# XL6009.net
KiCad netlist of a schematic drawn in Altium Designer
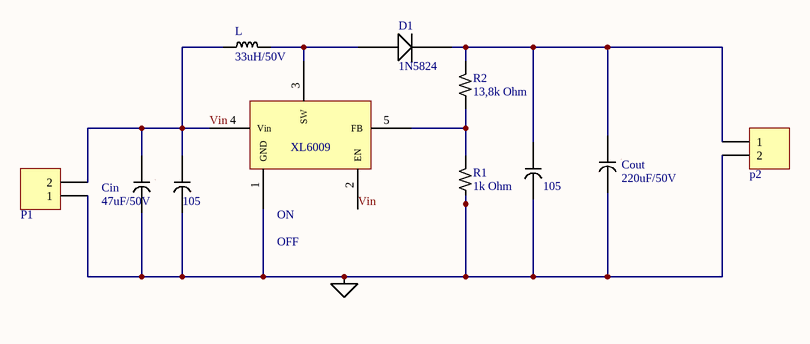
[diagram p0: XL6009.SchDoc]

(export (version "E")
  (design (tool "Eeschema 10.0.6"))
  (components
    (comp (ref "*") (value "Component_1") (libsource (lib "Schlib1") (part "Component_1")))
    (comp (ref "1") (value "105") (footprint "PCBComponent_1") (libsource (lib "Schlib1") (part "105")))
    (comp (ref "105") (value "105") (footprint "PCBComponent_1") (libsource (lib "Schlib1") (part "105")))
    (comp (ref "Cin")
      (value "47uF/50V")
      (footprint "Cout:PCBComponent_1")
      (libsource (lib "Schlib1") (part "capacitor"))
    )
    (comp (ref "Cout")
      (value "220uF/50V")
      (footprint "Cout:PCBComponent_1")
      (libsource (lib "Schlib1") (part "capacitor"))
    )
    (comp (ref "D1") (value "1N5824") (footprint "1N5824") (libsource (lib "Schlib1") (part "diode")))
    (comp (ref "L")
      (value "33uH/50V")
      (footprint "coil:PCBComponent_1")
      (libsource (lib "Schlib1") (part "Electrolytic Cap"))
    )
    (comp (ref "P1")
      (value "Domino 2")
      (footprint "DOMINO SMALL 2")
      (description "Domino, 2-Pin")
      (fields (field (name "PUBLISHER") "Altium Limited"))
      (libsource (lib "PIF_Library") (part "Domino 2"))
    )
    (comp (ref "p2")
      (value "Domino 2")
      (footprint "DOMINO SMALL 2")
      (description "Domino, 2-Pin")
      (fields (field (name "PUBLISHER") "Altium Limited"))
      (libsource (lib "") (part "Domino 2_1"))
    )
    (comp (ref "R1")
      (value "1k Ohm")
      (footprint "resistor0805:PCBComponent_1")
      (libsource (lib "Schlib1") (part "resistor"))
    )
    (comp (ref "R2")
      (value "13,8k Ohm")
      (footprint "resistor0805:PCBComponent_1")
      (libsource (lib "Schlib1") (part "resistor"))
    )
    (comp (ref "XL6009") (value "XL6009") (footprint "XL6009") (libsource (lib "Schlib1") (part "XL6009")))
  )
  (nets
    (net (code "1") (name "/Vin") (class "Default")
      (node (ref "105") (pin "1") (pinfunction "1_1") (pintype "passive"))
      (node (ref "Cin") (pin "1") (pinfunction "1_1") (pintype "passive"))
      (node (ref "L") (pin "1") (pinfunction "1_1") (pintype "passive"))
      (node (ref "P1") (pin "2") (pinfunction "2_2") (pintype "passive"))
      (node (ref "XL6009") (pin "2") (pinfunction "EN_2") (pintype "passive"))
      (node (ref "XL6009") (pin "4") (pinfunction "Vin_4") (pintype "passive"))
    )
    (net (code "2") (name "GND") (class "Default")
      (node (ref "1") (pin "2") (pinfunction "2_2") (pintype "passive"))
      (node (ref "105") (pin "2") (pinfunction "2_2") (pintype "passive"))
      (node (ref "Cin") (pin "2") (pinfunction "2_2") (pintype "passive"))
      (node (ref "Cout") (pin "2") (pinfunction "2_2") (pintype "passive"))
      (node (ref "P1") (pin "1") (pinfunction "1_1") (pintype "passive"))
      (node (ref "R1") (pin "1") (pinfunction "1_1") (pintype "passive"))
      (node (ref "XL6009") (pin "1") (pinfunction "GND_1") (pintype "passive"))
      (node (ref "p2") (pin "2") (pinfunction "2_2") (pintype "passive"))
    )
    (net (code "3") (name "Net-(1-Pad1)") (class "Default")
      (node (ref "1") (pin "1") (pinfunction "1_1") (pintype "passive"))
      (node (ref "Cout") (pin "1") (pinfunction "1_1") (pintype "passive"))
      (node (ref "D1") (pin "1") (pinfunction "1_1") (pintype "passive"))
      (node (ref "R2") (pin "2") (pinfunction "1_2") (pintype "passive"))
      (node (ref "p2") (pin "1") (pinfunction "1_1") (pintype "passive"))
    )
    (net (code "4") (name "Net-(XL6009-FB)") (class "Default")
      (node (ref "R1") (pin "2") (pinfunction "1_2") (pintype "passive"))
      (node (ref "R2") (pin "1") (pinfunction "1_1") (pintype "passive"))
      (node (ref "XL6009") (pin "5") (pinfunction "FB_5") (pintype "passive"))
    )
    (net (code "5") (name "Net-(XL6009-SW)") (class "Default")
      (node (ref "D1") (pin "2") (pinfunction "2_2") (pintype "passive"))
      (node (ref "L") (pin "2") (pinfunction "2_2") (pintype "passive"))
      (node (ref "XL6009") (pin "3") (pinfunction "SW_3") (pintype "passive"))
    )
  )
)
